# headerboard.net
KiCad netlist of a schematic drawn in EAGLE
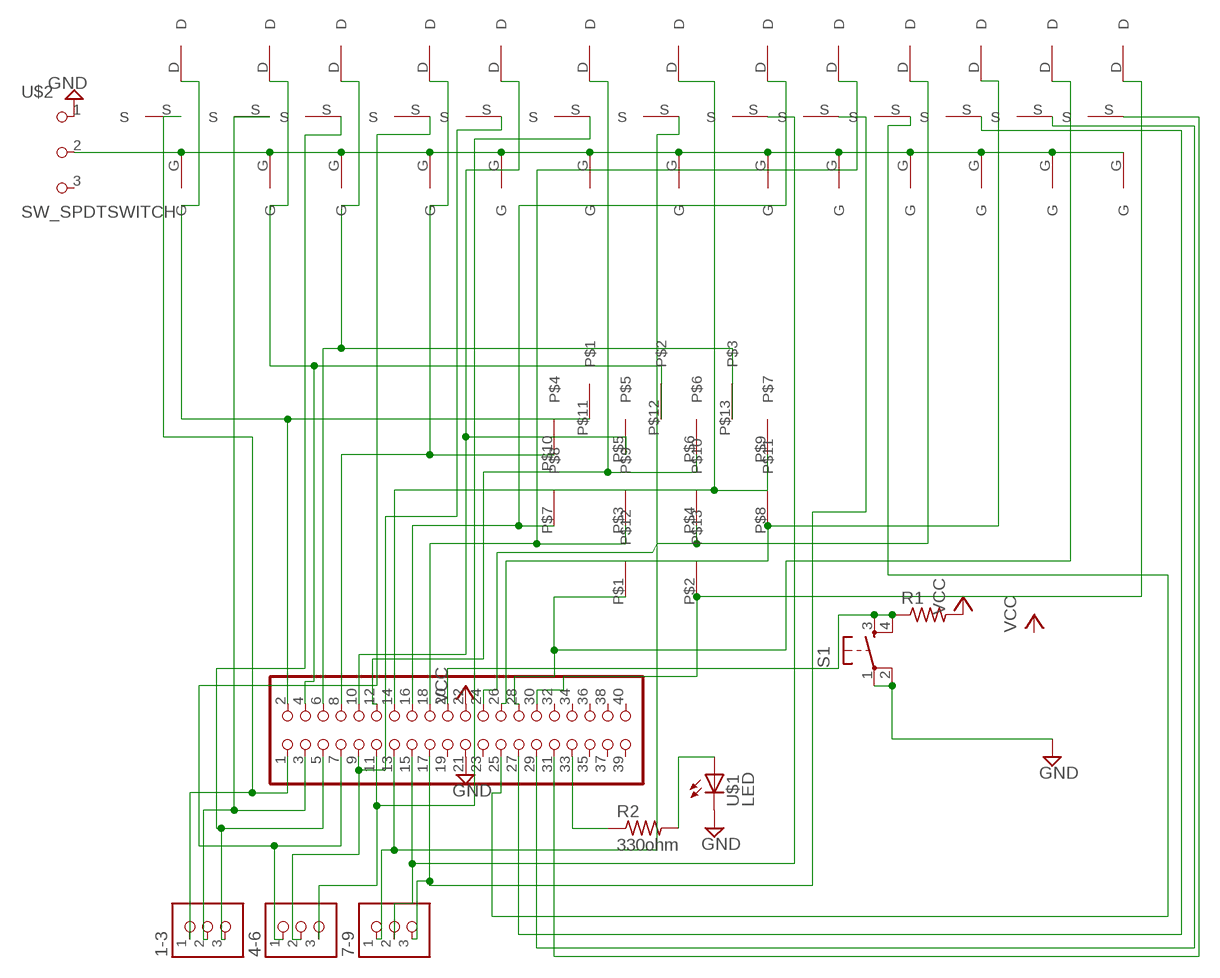
[diagram p0: schematic, sheet 1]

(export (version "E")
  (design (tool "Eeschema 10.0.6"))
  (components
    (comp (ref "1-3")
      (value "CONN_03_TERM'-FABLAB'")
      (footprint "eagle-import:ED555DS-3DS")
      (libsource (lib "eagle-import") (part "CONN_03_TERM'-FABLAB'"))
    )
    (comp (ref "4-6")
      (value "CONN_03_TERM'-FABLAB'")
      (footprint "eagle-import:ED555DS-3DS")
      (libsource (lib "eagle-import") (part "CONN_03_TERM'-FABLAB'"))
    )
    (comp (ref "7-9")
      (value "CONN_03_TERM'-FABLAB'")
      (footprint "eagle-import:ED555DS-3DS")
      (libsource (lib "eagle-import") (part "CONN_03_TERM'-FABLAB'"))
    )
    (comp (ref "JP1")
      (value "PINHD-2X20")
      (footprint "eagle-import:2X20")
      (libsource (lib "eagle-import") (part "PINHD-2X20"))
    )
    (comp (ref "R1")
      (value "R1206FAB")
      (footprint "eagle-import:R1206FAB")
      (libsource (lib "eagle-import") (part "R1206FAB"))
    )
    (comp (ref "R2")
      (value "330ohm")
      (footprint "eagle-import:R1206FAB")
      (libsource (lib "eagle-import") (part "R1206FAB"))
    )
    (comp (ref "S1")
      (value "SW_SWITCH_TACTILE_6MM6MM_SWITCH")
      (footprint "eagle-import:6MM_SWITCH")
      (libsource (lib "eagle-import") (part "SW_SWITCH_TACTILE_6MM6MM_SWITCH"))
    )
    (comp (ref "U$1")
      (value "LED")
      (footprint "eagle-import:LED1206")
      (libsource (lib "eagle-import") (part "LED"))
    )
    (comp (ref "U$2")
      (value "SW_SPDTSWITCH")
      (footprint "eagle-import:SPDTSWITCH")
      (libsource (lib "eagle-import") (part "SW_SPDTSWITCH"))
    )
    (comp (ref "U$3")
      (value "SOT23NMOS")
      (footprint "eagle-import:SOT23NMOS")
      (libsource (lib "eagle-import") (part "SOT23NMOS"))
    )
    (comp (ref "U$4")
      (value "SOT23NMOS")
      (footprint "eagle-import:SOT23NMOS")
      (libsource (lib "eagle-import") (part "SOT23NMOS"))
    )
    (comp (ref "U$5")
      (value "SOT23NMOS")
      (footprint "eagle-import:SOT23NMOS")
      (libsource (lib "eagle-import") (part "SOT23NMOS"))
    )
    (comp (ref "U$6")
      (value "SOT23NMOS")
      (footprint "eagle-import:SOT23NMOS")
      (libsource (lib "eagle-import") (part "SOT23NMOS"))
    )
    (comp (ref "U$7")
      (value "SOT23NMOS")
      (footprint "eagle-import:SOT23NMOS")
      (libsource (lib "eagle-import") (part "SOT23NMOS"))
    )
    (comp (ref "U$8")
      (value "SOT23NMOS")
      (footprint "eagle-import:SOT23NMOS")
      (libsource (lib "eagle-import") (part "SOT23NMOS"))
    )
    (comp (ref "U$9")
      (value "SOT23NMOS")
      (footprint "eagle-import:SOT23NMOS")
      (libsource (lib "eagle-import") (part "SOT23NMOS"))
    )
    (comp (ref "U$10")
      (value "SOT23NMOS")
      (footprint "eagle-import:SOT23NMOS")
      (libsource (lib "eagle-import") (part "SOT23NMOS"))
    )
    (comp (ref "U$11")
      (value "SOT23NMOS")
      (footprint "eagle-import:SOT23NMOS")
      (libsource (lib "eagle-import") (part "SOT23NMOS"))
    )
    (comp (ref "U$12")
      (value "SOT23NMOS")
      (footprint "eagle-import:SOT23NMOS")
      (libsource (lib "eagle-import") (part "SOT23NMOS"))
    )
    (comp (ref "U$13")
      (value "SOT23NMOS")
      (footprint "eagle-import:SOT23NMOS")
      (libsource (lib "eagle-import") (part "SOT23NMOS"))
    )
    (comp (ref "U$14")
      (value "SOT23NMOS")
      (footprint "eagle-import:SOT23NMOS")
      (libsource (lib "eagle-import") (part "SOT23NMOS"))
    )
    (comp (ref "U$15")
      (value "SOT23NMOS")
      (footprint "eagle-import:SOT23NMOS")
      (libsource (lib "eagle-import") (part "SOT23NMOS"))
    )
    (comp (ref "U$19")
      (value "13PINHEADER")
      (footprint "eagle-import:13HEADER")
      (libsource (lib "eagle-import") (part "13PINHEADER"))
    )
  )
  (nets
    (net (code "1") (name "GND") (class "Default")
      (node (ref "JP1") (pin "21") (pinfunction "21_21") (pintype "passive"))
      (node (ref "S1") (pin "1") (pinfunction "P_1") (pintype "passive"))
      (node (ref "S1") (pin "2") (pinfunction "P1_2") (pintype "passive"))
      (node (ref "U$1") (pin "2") (pinfunction "C_2") (pintype "passive"))
      (node (ref "U$2") (pin "1") (pinfunction "1_1") (pintype "passive"))
    )
    (net (code "2") (name "Net-(1-3-Pad1)") (class "Default")
      (node (ref "1-3") (pin "1") (pinfunction "1_1") (pintype "passive"))
      (node (ref "JP1") (pin "1") (pinfunction "1_1") (pintype "passive"))
      (node (ref "U$3") (pin "S") (pinfunction "S_S") (pintype "bidirectional"))
    )
    (net (code "3") (name "Net-(1-3-Pad2)") (class "Default")
      (node (ref "1-3") (pin "2") (pinfunction "2_2") (pintype "passive"))
      (node (ref "JP1") (pin "3") (pinfunction "3_3") (pintype "passive"))
      (node (ref "U$4") (pin "S") (pinfunction "S_S") (pintype "bidirectional"))
    )
    (net (code "4") (name "Net-(1-3-Pad3)") (class "Default")
      (node (ref "1-3") (pin "3") (pinfunction "3_3") (pintype "passive"))
      (node (ref "JP1") (pin "5") (pinfunction "5_5") (pintype "passive"))
      (node (ref "U$5") (pin "S") (pinfunction "S_S") (pintype "bidirectional"))
    )
    (net (code "5") (name "Net-(4-6-Pad1)") (class "Default")
      (node (ref "4-6") (pin "1") (pinfunction "1_1") (pintype "passive"))
      (node (ref "JP1") (pin "7") (pinfunction "7_7") (pintype "passive"))
      (node (ref "U$6") (pin "S") (pinfunction "S_S") (pintype "bidirectional"))
    )
    (net (code "6") (name "Net-(4-6-Pad2)") (class "Default")
      (node (ref "4-6") (pin "2") (pinfunction "2_2") (pintype "passive"))
      (node (ref "JP1") (pin "9") (pinfunction "9_9") (pintype "passive"))
      (node (ref "U$7") (pin "S") (pinfunction "S_S") (pintype "bidirectional"))
    )
    (net (code "7") (name "Net-(4-6-Pad3)") (class "Default")
      (node (ref "4-6") (pin "3") (pinfunction "3_3") (pintype "passive"))
      (node (ref "JP1") (pin "11") (pinfunction "11_11") (pintype "passive"))
      (node (ref "U$8") (pin "S") (pinfunction "S_S") (pintype "bidirectional"))
    )
    (net (code "8") (name "Net-(7-9-Pad1)") (class "Default")
      (node (ref "7-9") (pin "1") (pinfunction "1_1") (pintype "passive"))
      (node (ref "JP1") (pin "13") (pinfunction "13_13") (pintype "passive"))
      (node (ref "U$9") (pin "S") (pinfunction "S_S") (pintype "bidirectional"))
    )
    (net (code "9") (name "Net-(7-9-Pad2)") (class "Default")
      (node (ref "7-9") (pin "2") (pinfunction "2_2") (pintype "passive"))
      (node (ref "JP1") (pin "15") (pinfunction "15_15") (pintype "passive"))
      (node (ref "U$10") (pin "S") (pinfunction "S_S") (pintype "bidirectional"))
    )
    (net (code "10") (name "Net-(7-9-Pad3)") (class "Default")
      (node (ref "7-9") (pin "3") (pinfunction "3_3") (pintype "passive"))
      (node (ref "JP1") (pin "17") (pinfunction "17_17") (pintype "passive"))
      (node (ref "U$11") (pin "S") (pinfunction "S_S") (pintype "bidirectional"))
    )
    (net (code "11") (name "Net-(JP1-Pad10)") (class "Default")
      (node (ref "JP1") (pin "10") (pinfunction "10_10") (pintype "passive"))
      (node (ref "U$19") (pin "P$5") (pinfunction "P$5_P$5") (pintype "bidirectional"))
      (node (ref "U$7") (pin "D") (pinfunction "D_D") (pintype "bidirectional"))
    )
    (net (code "12") (name "Net-(JP1-Pad12)") (class "Default")
      (node (ref "JP1") (pin "12") (pinfunction "12_12") (pintype "passive"))
      (node (ref "U$19") (pin "P$6") (pinfunction "P$6_P$6") (pintype "bidirectional"))
      (node (ref "U$8") (pin "D") (pinfunction "D_D") (pintype "bidirectional"))
    )
    (net (code "13") (name "Net-(JP1-Pad25)") (class "Default")
      (node (ref "JP1") (pin "25") (pinfunction "25_25") (pintype "passive"))
      (node (ref "U$12") (pin "S") (pinfunction "S_S") (pintype "bidirectional"))
    )
    (net (code "14") (name "Net-(JP1-Pad27)") (class "Default")
      (node (ref "JP1") (pin "27") (pinfunction "27_27") (pintype "passive"))
      (node (ref "U$13") (pin "S") (pinfunction "S_S") (pintype "bidirectional"))
    )
    (net (code "15") (name "Net-(JP1-Pad29)") (class "Default")
      (node (ref "JP1") (pin "29") (pinfunction "29_29") (pintype "passive"))
      (node (ref "U$14") (pin "S") (pinfunction "S_S") (pintype "bidirectional"))
    )
    (net (code "16") (name "Net-(JP1-Pad31)") (class "Default")
      (node (ref "JP1") (pin "31") (pinfunction "31_31") (pintype "passive"))
      (node (ref "U$15") (pin "S") (pinfunction "S_S") (pintype "bidirectional"))
    )
    (net (code "17") (name "Net-(JP1-Pad33)") (class "Default")
      (node (ref "JP1") (pin "33") (pinfunction "33_33") (pintype "passive"))
      (node (ref "R2") (pin "1") (pinfunction "1_1") (pintype "passive"))
    )
    (net (code "18") (name "Net-(S1-S)") (class "Default")
      (node (ref "JP1") (pin "20") (pinfunction "20_20") (pintype "passive"))
      (node (ref "R1") (pin "1") (pinfunction "1_1") (pintype "passive"))
      (node (ref "S1") (pin "3") (pinfunction "S_3") (pintype "passive"))
      (node (ref "S1") (pin "4") (pinfunction "S1_4") (pintype "passive"))
    )
    (net (code "19") (name "Net-(U$1-A)") (class "Default")
      (node (ref "R2") (pin "2") (pinfunction "2_2") (pintype "passive"))
      (node (ref "U$1") (pin "1") (pinfunction "A_1") (pintype "passive"))
    )
    (net (code "20") (name "Net-(U$10-PadG)") (class "Default")
      (node (ref "U$10") (pin "G") (pinfunction "G_G") (pintype "bidirectional"))
      (node (ref "U$11") (pin "G") (pinfunction "G_G") (pintype "bidirectional"))
      (node (ref "U$12") (pin "G") (pinfunction "G_G") (pintype "bidirectional"))
      (node (ref "U$13") (pin "G") (pinfunction "G_G") (pintype "bidirectional"))
      (node (ref "U$14") (pin "G") (pinfunction "G_G") (pintype "bidirectional"))
      (node (ref "U$15") (pin "G") (pinfunction "G_G") (pintype "bidirectional"))
      (node (ref "U$2") (pin "2") (pinfunction "2_2") (pintype "passive"))
      (node (ref "U$3") (pin "G") (pinfunction "G_G") (pintype "bidirectional"))
      (node (ref "U$4") (pin "G") (pinfunction "G_G") (pintype "bidirectional"))
      (node (ref "U$5") (pin "G") (pinfunction "G_G") (pintype "bidirectional"))
      (node (ref "U$6") (pin "G") (pinfunction "G_G") (pintype "bidirectional"))
      (node (ref "U$7") (pin "G") (pinfunction "G_G") (pintype "bidirectional"))
      (node (ref "U$8") (pin "G") (pinfunction "G_G") (pintype "bidirectional"))
      (node (ref "U$9") (pin "G") (pinfunction "G_G") (pintype "bidirectional"))
    )
    (net (code "21") (name "Net-(U$19-P$1)") (class "Default")
      (node (ref "JP1") (pin "2") (pinfunction "2_2") (pintype "passive"))
      (node (ref "U$19") (pin "P$11") (pinfunction "P$1_P$11") (pintype "bidirectional"))
      (node (ref "U$3") (pin "D") (pinfunction "D_D") (pintype "bidirectional"))
    )
    (net (code "22") (name "Net-(U$19-P$2)") (class "Default")
      (node (ref "JP1") (pin "4") (pinfunction "4_4") (pintype "passive"))
      (node (ref "U$19") (pin "P$12") (pinfunction "P$2_P$12") (pintype "bidirectional"))
      (node (ref "U$4") (pin "D") (pinfunction "D_D") (pintype "bidirectional"))
    )
    (net (code "23") (name "Net-(U$19-P$3)") (class "Default")
      (node (ref "JP1") (pin "6") (pinfunction "6_6") (pintype "passive"))
      (node (ref "U$19") (pin "P$13") (pinfunction "P$3_P$13") (pintype "bidirectional"))
      (node (ref "U$5") (pin "D") (pinfunction "D_D") (pintype "bidirectional"))
    )
    (net (code "24") (name "Net-(U$19-P$4)") (class "Default")
      (node (ref "JP1") (pin "8") (pinfunction "8_8") (pintype "passive"))
      (node (ref "U$19") (pin "P$10") (pinfunction "P$4_P$10") (pintype "bidirectional"))
      (node (ref "U$6") (pin "D") (pinfunction "D_D") (pintype "bidirectional"))
    )
    (net (code "25") (name "Net-(U$19-P$7)") (class "Default")
      (node (ref "JP1") (pin "14") (pinfunction "14_14") (pintype "passive"))
      (node (ref "U$19") (pin "P$9") (pinfunction "P$7_P$9") (pintype "bidirectional"))
      (node (ref "U$9") (pin "D") (pinfunction "D_D") (pintype "bidirectional"))
    )
    (net (code "26") (name "Net-(U$19-P$8)") (class "Default")
      (node (ref "JP1") (pin "16") (pinfunction "16_16") (pintype "passive"))
      (node (ref "U$10") (pin "D") (pinfunction "D_D") (pintype "bidirectional"))
      (node (ref "U$19") (pin "P$7") (pinfunction "P$8_P$7") (pintype "bidirectional"))
    )
    (net (code "27") (name "Net-(U$19-P$9)") (class "Default")
      (node (ref "JP1") (pin "18") (pinfunction "18_18") (pintype "passive"))
      (node (ref "U$11") (pin "D") (pinfunction "D_D") (pintype "bidirectional"))
      (node (ref "U$19") (pin "P$3") (pinfunction "P$9_P$3") (pintype "bidirectional"))
    )
    (net (code "28") (name "Net-(U$19-P$10)") (class "Default")
      (node (ref "JP1") (pin "24") (pinfunction "24_24") (pintype "passive"))
      (node (ref "U$12") (pin "D") (pinfunction "D_D") (pintype "bidirectional"))
      (node (ref "U$19") (pin "P$4") (pinfunction "P$10_P$4") (pintype "bidirectional"))
    )
    (net (code "29") (name "Net-(U$19-P$11)") (class "Default")
      (node (ref "JP1") (pin "26") (pinfunction "26_26") (pintype "passive"))
      (node (ref "U$13") (pin "D") (pinfunction "D_D") (pintype "bidirectional"))
      (node (ref "U$19") (pin "P$8") (pinfunction "P$11_P$8") (pintype "bidirectional"))
    )
    (net (code "30") (name "Net-(U$19-P$12)") (class "Default")
      (node (ref "JP1") (pin "28") (pinfunction "28_28") (pintype "passive"))
      (node (ref "U$14") (pin "D") (pinfunction "D_D") (pintype "bidirectional"))
      (node (ref "U$19") (pin "P$1") (pinfunction "P$12_P$1") (pintype "bidirectional"))
    )
    (net (code "31") (name "Net-(U$19-P$13)") (class "Default")
      (node (ref "JP1") (pin "30") (pinfunction "30_30") (pintype "passive"))
      (node (ref "U$15") (pin "D") (pinfunction "D_D") (pintype "bidirectional"))
      (node (ref "U$19") (pin "P$2") (pinfunction "P$13_P$2") (pintype "bidirectional"))
    )
    (net (code "32") (name "VCC") (class "Default")
      (node (ref "JP1") (pin "22") (pinfunction "22_22") (pintype "passive"))
      (node (ref "R1") (pin "2") (pinfunction "2_2") (pintype "passive"))
    )
    (net (code "33") (name "unconnected-(JP1-Pad19)") (class "Default")
      (node (ref "JP1") (pin "19") (pinfunction "19_19") (pintype "passive"))
    )
    (net (code "34") (name "unconnected-(JP1-Pad23)") (class "Default")
      (node (ref "JP1") (pin "23") (pinfunction "23_23") (pintype "passive"))
    )
    (net (code "35") (name "unconnected-(JP1-Pad32)") (class "Default")
      (node (ref "JP1") (pin "32") (pinfunction "32_32") (pintype "passive"))
    )
    (net (code "36") (name "unconnected-(JP1-Pad34)") (class "Default")
      (node (ref "JP1") (pin "34") (pinfunction "34_34") (pintype "passive"))
    )
    (net (code "37") (name "unconnected-(JP1-Pad35)") (class "Default")
      (node (ref "JP1") (pin "35") (pinfunction "35_35") (pintype "passive"))
    )
    (net (code "38") (name "unconnected-(JP1-Pad36)") (class "Default")
      (node (ref "JP1") (pin "36") (pinfunction "36_36") (pintype "passive"))
    )
    (net (code "39") (name "unconnected-(JP1-Pad37)") (class "Default")
      (node (ref "JP1") (pin "37") (pinfunction "37_37") (pintype "passive"))
    )
    (net (code "40") (name "unconnected-(JP1-Pad38)") (class "Default")
      (node (ref "JP1") (pin "38") (pinfunction "38_38") (pintype "passive"))
    )
    (net (code "41") (name "unconnected-(JP1-Pad39)") (class "Default")
      (node (ref "JP1") (pin "39") (pinfunction "39_39") (pintype "passive"))
    )
    (net (code "42") (name "unconnected-(JP1-Pad40)") (class "Default")
      (node (ref "JP1") (pin "40") (pinfunction "40_40") (pintype "passive"))
    )
    (net (code "43") (name "unconnected-(U$2-Pad3)") (class "Default")
      (node (ref "U$2") (pin "3") (pinfunction "3_3") (pintype "passive"))
    )
  )
)
